# FlightPCB.net
KiCad netlist of a schematic drawn in EAGLE
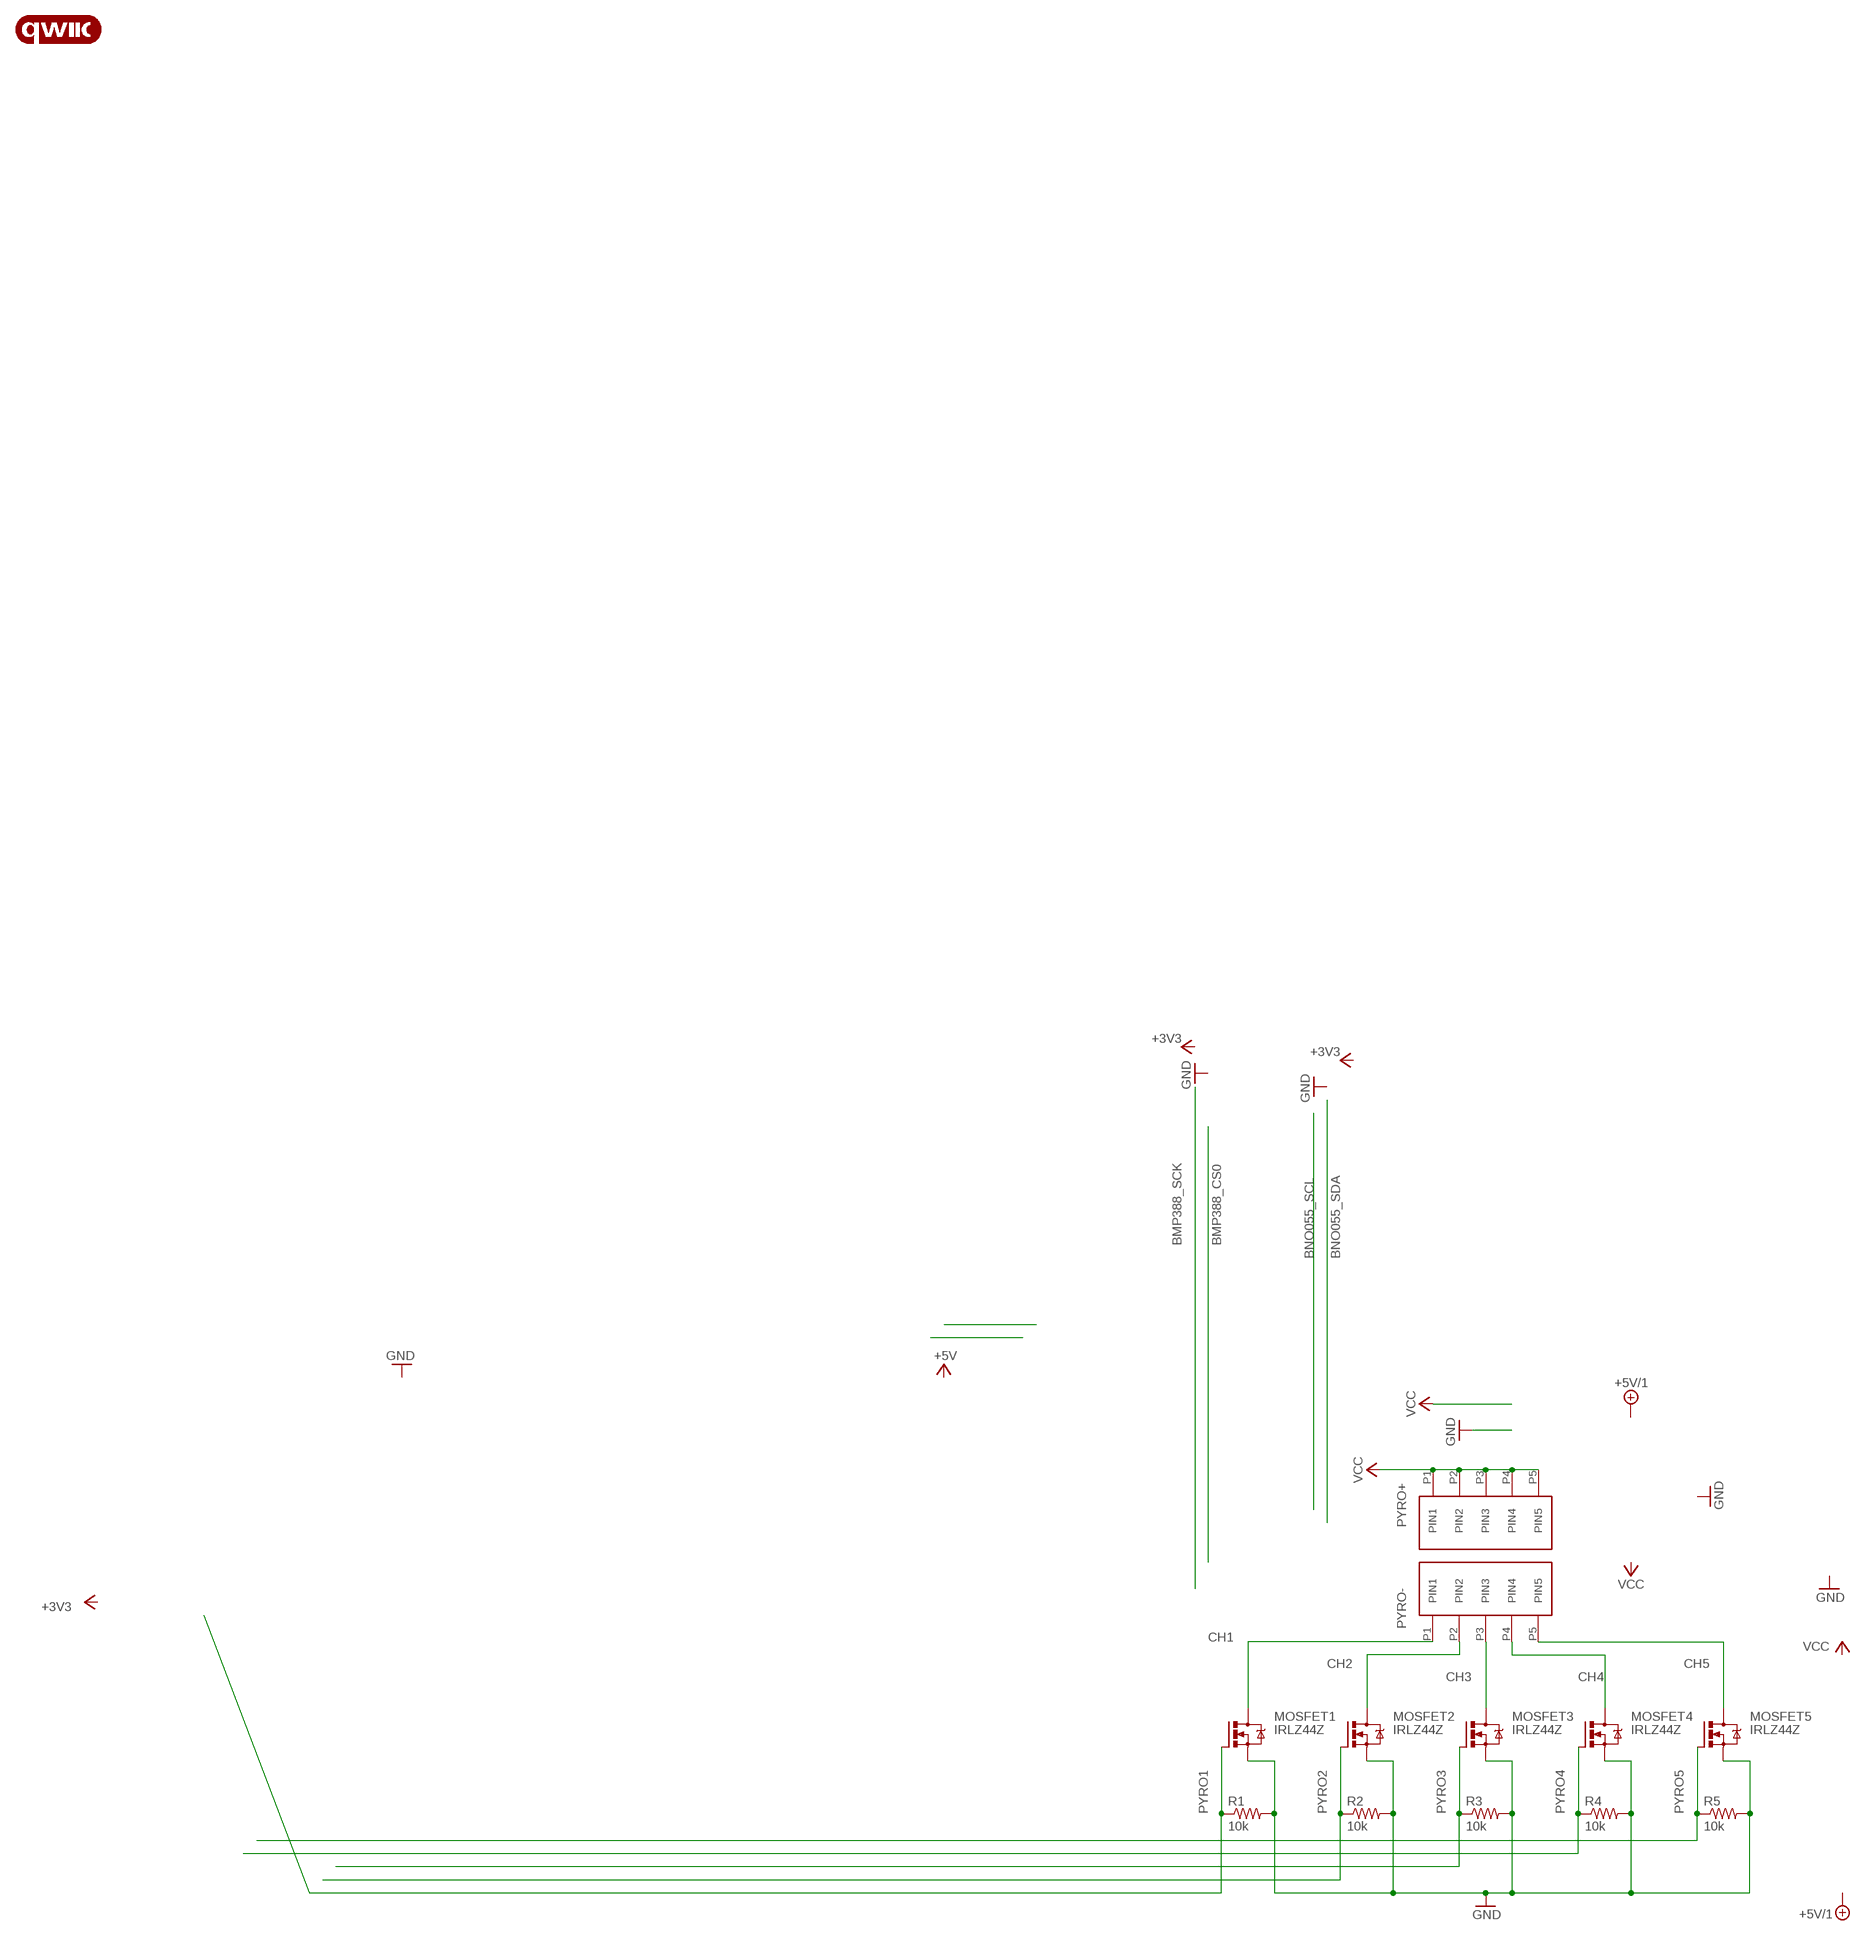
[diagram p0: schematic, sheet 1]

(export (version "E")
  (design (tool "Eeschema 10.0.6"))
  (components
    (comp (ref "LOGO1")
      (value "QWIIC_LOGO_3MM")
      (footprint "eagle-import:QWIIC_3MM")
      (libsource (lib "eagle-import") (part "QWIIC_LOGO_3MM"))
    )
    (comp (ref "MOSFET1")
      (value "IRLZ44Z")
      (footprint "eagle-import:TO220BH_SIMPLE")
      (libsource (lib "eagle-import") (part "IRLZ44Z"))
    )
    (comp (ref "MOSFET2")
      (value "IRLZ44Z")
      (footprint "eagle-import:TO220BH_SIMPLE")
      (libsource (lib "eagle-import") (part "IRLZ44Z"))
    )
    (comp (ref "MOSFET3")
      (value "IRLZ44Z")
      (footprint "eagle-import:TO220BH_SIMPLE")
      (libsource (lib "eagle-import") (part "IRLZ44Z"))
    )
    (comp (ref "MOSFET4")
      (value "IRLZ44Z")
      (footprint "eagle-import:TO220BH_SIMPLE")
      (libsource (lib "eagle-import") (part "IRLZ44Z"))
    )
    (comp (ref "MOSFET5")
      (value "IRLZ44Z")
      (footprint "eagle-import:TO220BH_SIMPLE")
      (libsource (lib "eagle-import") (part "IRLZ44Z"))
    )
    (comp (ref "PYRO+")
      (value "TERMINAL_BLOCK_5_PIN_5MM")
      (footprint "eagle-import:TERMINAL_BLOCK_5_PIN_5MM")
      (libsource (lib "eagle-import") (part "TERMINAL_BLOCK_5_PIN_5MM"))
    )
    (comp (ref "PYRO-")
      (value "TERMINAL_BLOCK_5_PIN_5MM")
      (footprint "eagle-import:TERMINAL_BLOCK_5_PIN_5MM")
      (libsource (lib "eagle-import") (part "TERMINAL_BLOCK_5_PIN_5MM"))
    )
    (comp (ref "R1")
      (value "10k")
      (footprint "eagle-import:0204_7")
      (libsource (lib "eagle-import") (part "R-US_0204/7"))
    )
    (comp (ref "R2")
      (value "10k")
      (footprint "eagle-import:0204_7")
      (libsource (lib "eagle-import") (part "R-US_0204/7"))
    )
    (comp (ref "R3")
      (value "10k")
      (footprint "eagle-import:0204_7")
      (libsource (lib "eagle-import") (part "R-US_0204/7"))
    )
    (comp (ref "R4")
      (value "10k")
      (footprint "eagle-import:0204_7")
      (libsource (lib "eagle-import") (part "R-US_0204/7"))
    )
    (comp (ref "R5")
      (value "10k")
      (footprint "eagle-import:0204_7")
      (libsource (lib "eagle-import") (part "R-US_0204/7"))
    )
  )
  (nets
    (net (code "8") (name "/CH1") (class "Default")
      (node (ref "MOSFET1") (pin "D") (pinfunction "D_D") (pintype "passive"))
      (node (ref "PYRO-") (pin "P1") (pinfunction "PIN1_P1") (pintype "bidirectional"))
    )
    (net (code "9") (name "/CH2") (class "Default")
      (node (ref "MOSFET2") (pin "D") (pinfunction "D_D") (pintype "passive"))
      (node (ref "PYRO-") (pin "P2") (pinfunction "PIN2_P2") (pintype "bidirectional"))
    )
    (net (code "10") (name "/CH3") (class "Default")
      (node (ref "MOSFET3") (pin "D") (pinfunction "D_D") (pintype "passive"))
      (node (ref "PYRO-") (pin "P3") (pinfunction "PIN3_P3") (pintype "bidirectional"))
    )
    (net (code "11") (name "/CH4") (class "Default")
      (node (ref "MOSFET4") (pin "D") (pinfunction "D_D") (pintype "passive"))
      (node (ref "PYRO-") (pin "P4") (pinfunction "PIN4_P4") (pintype "bidirectional"))
    )
    (net (code "12") (name "/CH5") (class "Default")
      (node (ref "MOSFET5") (pin "D") (pinfunction "D_D") (pintype "passive"))
      (node (ref "PYRO-") (pin "P5") (pinfunction "PIN5_P5") (pintype "bidirectional"))
    )
    (net (code "13") (name "/PYRO1") (class "Default")
      (node (ref "MOSFET1") (pin "G") (pinfunction "G_G") (pintype "passive"))
      (node (ref "R1") (pin "1") (pinfunction "1_1") (pintype "passive"))
    )
    (net (code "14") (name "/PYRO2") (class "Default")
      (node (ref "MOSFET2") (pin "G") (pinfunction "G_G") (pintype "passive"))
      (node (ref "R2") (pin "1") (pinfunction "1_1") (pintype "passive"))
    )
    (net (code "15") (name "/PYRO3") (class "Default")
      (node (ref "MOSFET3") (pin "G") (pinfunction "G_G") (pintype "passive"))
      (node (ref "R3") (pin "1") (pinfunction "1_1") (pintype "passive"))
    )
    (net (code "16") (name "/PYRO4") (class "Default")
      (node (ref "MOSFET4") (pin "G") (pinfunction "G_G") (pintype "passive"))
      (node (ref "R4") (pin "1") (pinfunction "1_1") (pintype "passive"))
    )
    (net (code "17") (name "/PYRO5") (class "Default")
      (node (ref "MOSFET5") (pin "G") (pinfunction "G_G") (pintype "passive"))
      (node (ref "R5") (pin "1") (pinfunction "1_1") (pintype "passive"))
    )
    (net (code "18") (name "GND") (class "Default")
      (node (ref "MOSFET1") (pin "S") (pinfunction "S_S") (pintype "passive"))
      (node (ref "MOSFET2") (pin "S") (pinfunction "S_S") (pintype "passive"))
      (node (ref "MOSFET3") (pin "S") (pinfunction "S_S") (pintype "passive"))
      (node (ref "MOSFET4") (pin "S") (pinfunction "S_S") (pintype "passive"))
      (node (ref "MOSFET5") (pin "S") (pinfunction "S_S") (pintype "passive"))
      (node (ref "R1") (pin "2") (pinfunction "2_2") (pintype "passive"))
      (node (ref "R2") (pin "2") (pinfunction "2_2") (pintype "passive"))
      (node (ref "R3") (pin "2") (pinfunction "2_2") (pintype "passive"))
      (node (ref "R4") (pin "2") (pinfunction "2_2") (pintype "passive"))
      (node (ref "R5") (pin "2") (pinfunction "2_2") (pintype "passive"))
    )
    (net (code "19") (name "VCC") (class "Default")
      (node (ref "PYRO+") (pin "P1") (pinfunction "PIN1_P1") (pintype "bidirectional"))
      (node (ref "PYRO+") (pin "P2") (pinfunction "PIN2_P2") (pintype "bidirectional"))
      (node (ref "PYRO+") (pin "P3") (pinfunction "PIN3_P3") (pintype "bidirectional"))
      (node (ref "PYRO+") (pin "P4") (pinfunction "PIN4_P4") (pintype "bidirectional"))
      (node (ref "PYRO+") (pin "P5") (pinfunction "PIN5_P5") (pintype "bidirectional"))
    )
  )
)
